# card-shuffling-dealing-machine.net
KiCad netlist of a schematic drawn in Altium Designer
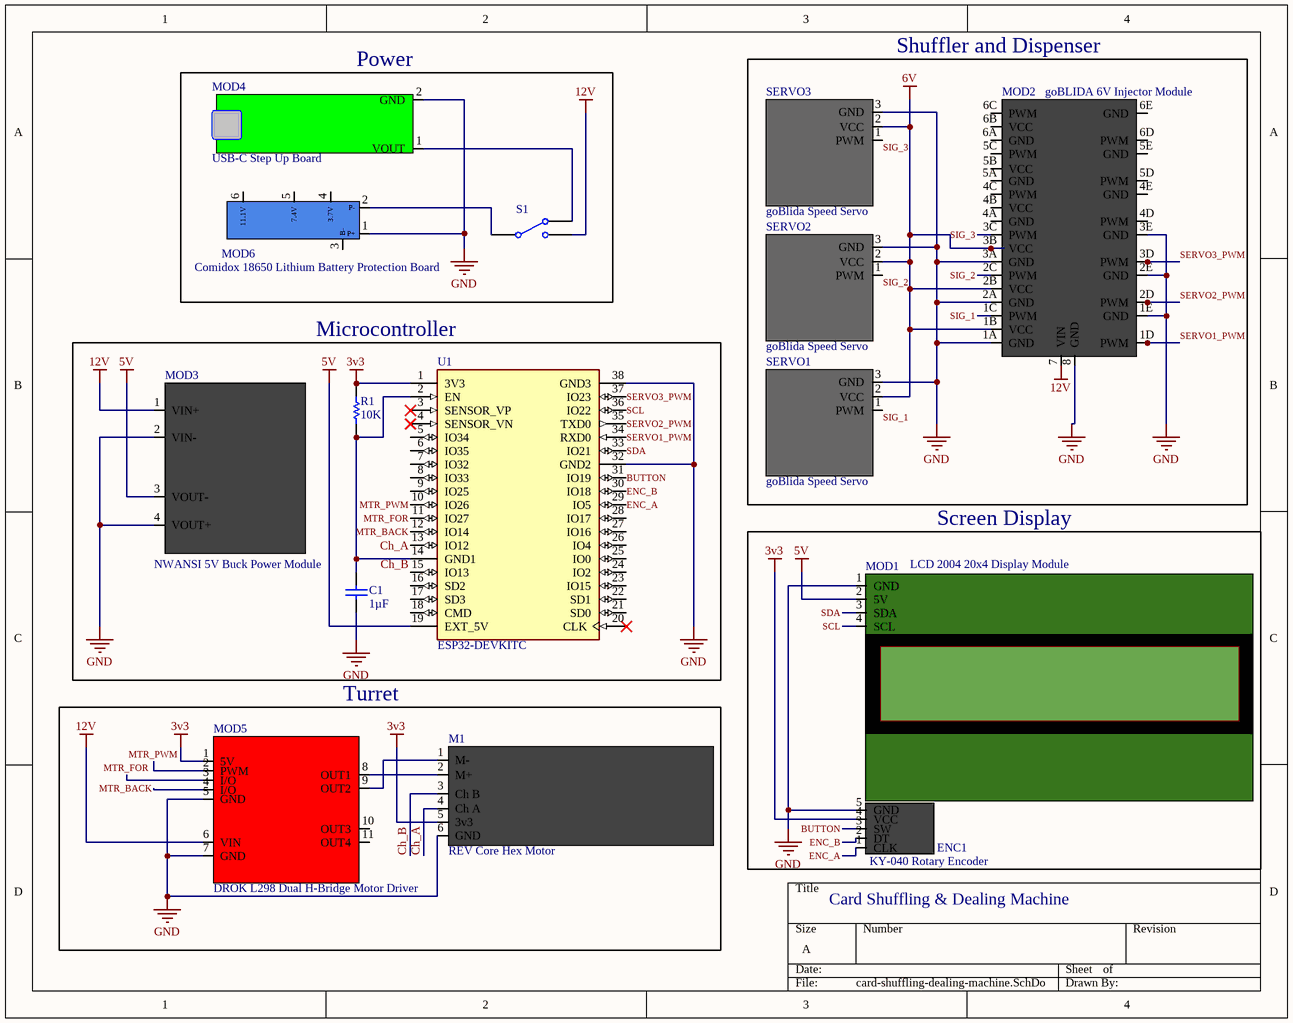
[diagram p0: card-shuffling-dealing-machine.SchDoc]

(export (version "E")
  (design (tool "Eeschema 10.0.6"))
  (components
    (comp (ref "C1")
      (value "1µF")
      (description "Capacitor")
      (libsource (lib "Simulation Generic Components") (part "Capacitor"))
    )
    (comp (ref "ENC1")
      (value "KY-040 Rotary Encoder")
      (description "5V Rotary Encoder Module 360 Degree Switch Encoder")
      (libsource (lib "CustomParts") (part "KY-040_Rotary_Encoder"))
    )
    (comp (ref "M1")
      (value "REV Core Hex Motor")
      (description "12 V DC Gear Motor with Integrated Encoder")
      (libsource (lib "CustomParts") (part "REV_Core_Hex_Motor"))
    )
    (comp (ref "MOD1")
      (value "LCD 2004 20x4 Display Module")
      (description "LCD 2004 I2C (TWI) 20x4 Display Module")
      (libsource (lib "CustomParts") (part "LCD_2004_20x4_Display_Module"))
    )
    (comp (ref "MOD2")
      (value "goBLIDA 6V Injector Module")
      (description "8-15V Input to 6V 24A Injector Module")
      (libsource (lib "CustomParts") (part "goBLIDA_6V_Injector_Module"))
    )
    (comp (ref "MOD3")
      (value "NWANSI 5V Buck Power Module")
      (description "DC 12/24V to 5V 3A/15W Power Converter Buck Power Module")
      (libsource (lib "CustomParts") (part "NWANSI_Buck_Power_Module"))
    )
    (comp (ref "MOD4")
      (value "USB-C Step Up Board")
      (description "Converts USB C 5V to 12.6V")
      (libsource (lib "CustomParts") (part "Type_C_Step_Up_Boost"))
    )
    (comp (ref "MOD5")
      (value "DROK L298 Dual H-Bridge Motor Driver")
      (description "7A Dual DC Motor Controller Board (6.5V-27V Input, Optocoupler Isolated)")
      (libsource (lib "CustomParts") (part "L298_Dual_H_Bridge_Motor_Driver"))
    )
    (comp (ref "MOD6")
      (value "Comidox 18650 Lithium Battery Protection Board")
      (description "3S 12V 10A 18650 Lithium Battery Protection Board")
      (libsource (lib "CustomParts") (part "Comidox_18650_Lithium_Battery_Protection_Board"))
    )
    (comp (ref "R1")
      (value "10K")
      (description "Resistor")
      (libsource (lib "Simulation Generic Components") (part "Resistor"))
    )
    (comp (ref "S1")
      (value "Single-Pole, Double-Throw Switch")
      (libsource (lib "Simulation Generic Components") (part "SPDT SW"))
    )
    (comp (ref "SERVO1")
      (value "goBlida Speed Servo")
      (description "Dual-Mode Servo (PWM/Continuous)")
      (libsource (lib "CustomParts") (part "goBIDA_Speed_Servo"))
    )
    (comp (ref "SERVO2")
      (value "goBlida Speed Servo")
      (description "Dual-Mode Servo (PWM/Continuous)")
      (libsource (lib "CustomParts") (part "goBIDA_Speed_Servo"))
    )
    (comp (ref "SERVO3")
      (value "goBlida Speed Servo")
      (description "Dual-Mode Servo (PWM/Continuous)")
      (libsource (lib "CustomParts") (part "goBIDA_Speed_Servo"))
    )
    (comp (ref "U1")
      (value "ESP32-DEVKITC")
      (footprint "MODULE_ESP32-DEVKITC")
      (fields (field (name "MF") "Espressif Systems"))
      (libsource (lib "Gaucho Racing") (part "ESP32-DEVKITC"))
    )
  )
  (nets
    (net (code "1") (name "/BUTTON") (class "Default")
      (node (ref "ENC1") (pin "3") (pinfunction "SW_3") (pintype "passive"))
      (node (ref "U1") (pin "31") (pinfunction "IO19_31") (pintype "bidirectional"))
    )
    (net (code "2") (name "/Ch_A") (class "Default")
      (node (ref "M1") (pin "4") (pinfunction "Ch_A_4") (pintype "passive"))
      (node (ref "U1") (pin "13") (pinfunction "IO12_13") (pintype "bidirectional"))
    )
    (net (code "3") (name "/Ch_B") (class "Default")
      (node (ref "M1") (pin "3") (pinfunction "Ch_B_3") (pintype "passive"))
      (node (ref "U1") (pin "15") (pinfunction "IO13_15") (pintype "bidirectional"))
    )
    (net (code "4") (name "/ENC_A") (class "Default")
      (node (ref "ENC1") (pin "1") (pinfunction "CLK_1") (pintype "passive"))
      (node (ref "U1") (pin "29") (pinfunction "IO5_29") (pintype "bidirectional"))
    )
    (net (code "5") (name "/ENC_B") (class "Default")
      (node (ref "ENC1") (pin "2") (pinfunction "DT_2") (pintype "passive"))
      (node (ref "U1") (pin "30") (pinfunction "IO18_30") (pintype "bidirectional"))
    )
    (net (code "6") (name "/MTR_BACK") (class "Default")
      (node (ref "MOD5") (pin "4") (pinfunction "I/O_4") (pintype "bidirectional"))
      (node (ref "U1") (pin "12") (pinfunction "IO14_12") (pintype "bidirectional"))
    )
    (net (code "7") (name "/MTR_FOR") (class "Default")
      (node (ref "MOD5") (pin "3") (pinfunction "I/O_3") (pintype "bidirectional"))
      (node (ref "U1") (pin "11") (pinfunction "IO27_11") (pintype "bidirectional"))
    )
    (net (code "8") (name "/MTR_PWM") (class "Default")
      (node (ref "MOD5") (pin "2") (pinfunction "PWM_2") (pintype "passive"))
      (node (ref "U1") (pin "10") (pinfunction "IO26_10") (pintype "bidirectional"))
    )
    (net (code "9") (name "/SCL") (class "Default")
      (node (ref "MOD1") (pin "4") (pinfunction "SCL_4") (pintype "passive"))
      (node (ref "U1") (pin "36") (pinfunction "IO22_36") (pintype "bidirectional"))
    )
    (net (code "10") (name "/SDA") (class "Default")
      (node (ref "MOD1") (pin "3") (pinfunction "SDA_3") (pintype "passive"))
      (node (ref "U1") (pin "33") (pinfunction "IO21_33") (pintype "bidirectional"))
    )
    (net (code "11") (name "/SERVO1_PWM") (class "Default")
      (node (ref "MOD2") (pin "1D") (pinfunction "PWM_1D") (pintype "passive"))
      (node (ref "U1") (pin "34") (pinfunction "RXD0_34") (pintype "input"))
    )
    (net (code "12") (name "/SERVO2_PWM") (class "Default")
      (node (ref "MOD2") (pin "2D") (pinfunction "PWM_2D") (pintype "passive"))
      (node (ref "U1") (pin "35") (pinfunction "TXD0_35") (pintype "output"))
    )
    (net (code "13") (name "/SERVO3_PWM") (class "Default")
      (node (ref "MOD2") (pin "3D") (pinfunction "PWM_3D") (pintype "passive"))
      (node (ref "U1") (pin "37") (pinfunction "IO23_37") (pintype "bidirectional"))
    )
    (net (code "14") (name "/SIG_1") (class "Default")
      (node (ref "MOD2") (pin "1C") (pinfunction "PWM_1C") (pintype "passive"))
      (node (ref "SERVO1") (pin "1") (pinfunction "PWM_1") (pintype "passive"))
    )
    (net (code "15") (name "/SIG_2") (class "Default")
      (node (ref "MOD2") (pin "2C") (pinfunction "PWM_2C") (pintype "passive"))
      (node (ref "SERVO2") (pin "1") (pinfunction "PWM_1") (pintype "passive"))
    )
    (net (code "16") (name "/SIG_3") (class "Default")
      (node (ref "MOD2") (pin "3C") (pinfunction "PWM_3C") (pintype "passive"))
      (node (ref "SERVO3") (pin "1") (pinfunction "PWM_1") (pintype "passive"))
    )
    (net (code "17") (name "3v3") (class "Default")
      (node (ref "ENC1") (pin "4") (pinfunction "VCC_4") (pintype "passive"))
      (node (ref "M1") (pin "5") (pinfunction "3v3_5") (pintype "passive"))
      (node (ref "MOD5") (pin "1") (pinfunction "5V_1") (pintype "passive"))
      (node (ref "R1") (pin "2") (pinfunction "2_2") (pintype "passive"))
      (node (ref "U1") (pin "1") (pinfunction "3V3_1") (pintype "power_in"))
    )
    (net (code "18") (name "5V") (class "Default")
      (node (ref "MOD1") (pin "2") (pinfunction "5V_2") (pintype "passive"))
      (node (ref "MOD3") (pin "3") (pinfunction "VOUT-_3") (pintype "power_in"))
      (node (ref "U1") (pin "19") (pinfunction "EXT_5V_19") (pintype "power_in"))
    )
    (net (code "19") (name "6V") (class "Default")
      (node (ref "MOD2") (pin "1B") (pinfunction "VCC_1B") (pintype "passive"))
      (node (ref "MOD2") (pin "2B") (pinfunction "VCC_2B") (pintype "passive"))
      (node (ref "MOD2") (pin "3B") (pinfunction "VCC_3B") (pintype "passive"))
      (node (ref "SERVO1") (pin "2") (pinfunction "VCC_2") (pintype "passive"))
      (node (ref "SERVO2") (pin "2") (pinfunction "VCC_2") (pintype "passive"))
      (node (ref "SERVO3") (pin "2") (pinfunction "VCC_2") (pintype "passive"))
    )
    (net (code "20") (name "12V") (class "Default")
      (node (ref "MOD2") (pin "7") (pinfunction "VIN_7") (pintype "passive"))
      (node (ref "MOD3") (pin "1") (pinfunction "VIN+_1") (pintype "input"))
      (node (ref "MOD5") (pin "6") (pinfunction "VIN_6") (pintype "passive"))
      (node (ref "S1") (pin "2") (pinfunction "2_2") (pintype "passive"))
    )
    (net (code "21") (name "GND") (class "Default")
      (node (ref "C1") (pin "1") (pinfunction "1_1") (pintype "passive"))
      (node (ref "ENC1") (pin "5") (pinfunction "GND_5") (pintype "passive"))
      (node (ref "M1") (pin "6") (pinfunction "GND_6") (pintype "passive"))
      (node (ref "MOD1") (pin "1") (pinfunction "GND_1") (pintype "passive"))
      (node (ref "MOD2") (pin "1A") (pinfunction "GND_1A") (pintype "passive"))
      (node (ref "MOD2") (pin "1E") (pinfunction "GND_1E") (pintype "passive"))
      (node (ref "MOD2") (pin "2A") (pinfunction "GND_2A") (pintype "passive"))
      (node (ref "MOD2") (pin "2E") (pinfunction "GND_2E") (pintype "passive"))
      (node (ref "MOD2") (pin "3A") (pinfunction "GND_3A") (pintype "passive"))
      (node (ref "MOD2") (pin "3E") (pinfunction "GND_3E") (pintype "passive"))
      (node (ref "MOD2") (pin "8") (pinfunction "GND_8") (pintype "passive"))
      (node (ref "MOD3") (pin "2") (pinfunction "VIN-_2") (pintype "input"))
      (node (ref "MOD3") (pin "4") (pinfunction "VOUT+_4") (pintype "power_in"))
      (node (ref "MOD4") (pin "2") (pinfunction "GND_2") (pintype "passive"))
      (node (ref "MOD5") (pin "5") (pinfunction "GND_5") (pintype "passive"))
      (node (ref "MOD5") (pin "7") (pinfunction "GND_7") (pintype "passive"))
      (node (ref "MOD6") (pin "1") (pinfunction "P+_1") (pintype "passive"))
      (node (ref "SERVO1") (pin "3") (pinfunction "GND_3") (pintype "passive"))
      (node (ref "SERVO2") (pin "3") (pinfunction "GND_3") (pintype "passive"))
      (node (ref "SERVO3") (pin "3") (pinfunction "GND_3") (pintype "passive"))
      (node (ref "U1") (pin "32") (pinfunction "GND2_32") (pintype "power_in"))
      (node (ref "U1") (pin "38") (pinfunction "GND3_38") (pintype "power_in"))
    )
    (net (code "22") (name "Net-(M1-M+)") (class "Default")
      (node (ref "M1") (pin "2") (pinfunction "M+_2") (pintype "passive"))
      (node (ref "MOD5") (pin "8") (pinfunction "OUT1_8") (pintype "output"))
    )
    (net (code "23") (name "Net-(M1-M-)") (class "Default")
      (node (ref "M1") (pin "1") (pinfunction "M-_1") (pintype "passive"))
      (node (ref "MOD5") (pin "9") (pinfunction "OUT2_9") (pintype "output"))
    )
    (net (code "24") (name "Net-(MOD4-VOUT)") (class "Default")
      (node (ref "MOD4") (pin "1") (pinfunction "VOUT_1") (pintype "passive"))
      (node (ref "S1") (pin "3") (pinfunction "3_3") (pintype "passive"))
    )
    (net (code "25") (name "Net-(MOD6-P-)") (class "Default")
      (node (ref "MOD6") (pin "2") (pinfunction "P-_2") (pintype "passive"))
      (node (ref "S1") (pin "1") (pinfunction "1_1") (pintype "passive"))
    )
    (net (code "26") (name "Net-(U1-EN)") (class "Default")
      (node (ref "C1") (pin "2") (pinfunction "2_2") (pintype "passive"))
      (node (ref "R1") (pin "1") (pinfunction "1_1") (pintype "passive"))
      (node (ref "U1") (pin "14") (pinfunction "GND1_14") (pintype "power_in"))
      (node (ref "U1") (pin "2") (pinfunction "EN_2") (pintype "input"))
    )
    (net (code "27") (name "unconnected-(MOD2-GND-Pad4A)") (class "Default")
      (node (ref "MOD2") (pin "4A") (pinfunction "GND_4A") (pintype "passive"))
    )
    (net (code "28") (name "unconnected-(MOD2-GND-Pad4E)") (class "Default")
      (node (ref "MOD2") (pin "4E") (pinfunction "GND_4E") (pintype "passive"))
    )
    (net (code "29") (name "unconnected-(MOD2-GND-Pad5A)") (class "Default")
      (node (ref "MOD2") (pin "5A") (pinfunction "GND_5A") (pintype "passive"))
    )
    (net (code "30") (name "unconnected-(MOD2-GND-Pad5E)") (class "Default")
      (node (ref "MOD2") (pin "5E") (pinfunction "GND_5E") (pintype "passive"))
    )
    (net (code "31") (name "unconnected-(MOD2-GND-Pad6A)") (class "Default")
      (node (ref "MOD2") (pin "6A") (pinfunction "GND_6A") (pintype "passive"))
    )
    (net (code "32") (name "unconnected-(MOD2-GND-Pad6E)") (class "Default")
      (node (ref "MOD2") (pin "6E") (pinfunction "GND_6E") (pintype "passive"))
    )
    (net (code "33") (name "unconnected-(MOD2-PWM-Pad4C)") (class "Default")
      (node (ref "MOD2") (pin "4C") (pinfunction "PWM_4C") (pintype "passive"))
    )
    (net (code "34") (name "unconnected-(MOD2-PWM-Pad4D)") (class "Default")
      (node (ref "MOD2") (pin "4D") (pinfunction "PWM_4D") (pintype "passive"))
    )
    (net (code "35") (name "unconnected-(MOD2-PWM-Pad5C)") (class "Default")
      (node (ref "MOD2") (pin "5C") (pinfunction "PWM_5C") (pintype "passive"))
    )
    (net (code "36") (name "unconnected-(MOD2-PWM-Pad5D)") (class "Default")
      (node (ref "MOD2") (pin "5D") (pinfunction "PWM_5D") (pintype "passive"))
    )
    (net (code "37") (name "unconnected-(MOD2-PWM-Pad6C)") (class "Default")
      (node (ref "MOD2") (pin "6C") (pinfunction "PWM_6C") (pintype "passive"))
    )
    (net (code "38") (name "unconnected-(MOD2-PWM-Pad6D)") (class "Default")
      (node (ref "MOD2") (pin "6D") (pinfunction "PWM_6D") (pintype "passive"))
    )
    (net (code "39") (name "unconnected-(MOD2-VCC-Pad4B)") (class "Default")
      (node (ref "MOD2") (pin "4B") (pinfunction "VCC_4B") (pintype "passive"))
    )
    (net (code "40") (name "unconnected-(MOD2-VCC-Pad5B)") (class "Default")
      (node (ref "MOD2") (pin "5B") (pinfunction "VCC_5B") (pintype "passive"))
    )
    (net (code "41") (name "unconnected-(MOD2-VCC-Pad6B)") (class "Default")
      (node (ref "MOD2") (pin "6B") (pinfunction "VCC_6B") (pintype "passive"))
    )
    (net (code "42") (name "unconnected-(MOD5-OUT3-Pad10)") (class "Default")
      (node (ref "MOD5") (pin "10") (pinfunction "OUT3_10") (pintype "output"))
    )
    (net (code "43") (name "unconnected-(MOD5-OUT4-Pad11)") (class "Default")
      (node (ref "MOD5") (pin "11") (pinfunction "OUT4_11") (pintype "output"))
    )
    (net (code "44") (name "unconnected-(MOD6-3.7V-Pad4)") (class "Default")
      (node (ref "MOD6") (pin "4") (pinfunction "3.7V_4") (pintype "passive"))
    )
    (net (code "45") (name "unconnected-(MOD6-7.4V-Pad5)") (class "Default")
      (node (ref "MOD6") (pin "5") (pinfunction "7.4V_5") (pintype "passive"))
    )
    (net (code "46") (name "unconnected-(MOD6-11.1V-Pad6)") (class "Default")
      (node (ref "MOD6") (pin "6") (pinfunction "11.1V_6") (pintype "passive"))
    )
    (net (code "47") (name "unconnected-(MOD6-B--Pad3)") (class "Default")
      (node (ref "MOD6") (pin "3") (pinfunction "B-_3") (pintype "passive"))
    )
    (net (code "48") (name "unconnected-(U1-CLK-Pad20)") (class "Default")
      (node (ref "U1") (pin "20") (pinfunction "CLK_20") (pintype "input+no_connect"))
    )
    (net (code "49") (name "unconnected-(U1-CMD-Pad18)") (class "Default")
      (node (ref "U1") (pin "18") (pinfunction "CMD_18") (pintype "bidirectional"))
    )
    (net (code "50") (name "unconnected-(U1-IO0-Pad25)") (class "Default")
      (node (ref "U1") (pin "25") (pinfunction "IO0_25") (pintype "bidirectional"))
    )
    (net (code "51") (name "unconnected-(U1-IO2-Pad24)") (class "Default")
      (node (ref "U1") (pin "24") (pinfunction "IO2_24") (pintype "bidirectional"))
    )
    (net (code "52") (name "unconnected-(U1-IO4-Pad26)") (class "Default")
      (node (ref "U1") (pin "26") (pinfunction "IO4_26") (pintype "bidirectional"))
    )
    (net (code "53") (name "unconnected-(U1-IO15-Pad23)") (class "Default")
      (node (ref "U1") (pin "23") (pinfunction "IO15_23") (pintype "bidirectional"))
    )
    (net (code "54") (name "unconnected-(U1-IO16-Pad27)") (class "Default")
      (node (ref "U1") (pin "27") (pinfunction "IO16_27") (pintype "bidirectional"))
    )
    (net (code "55") (name "unconnected-(U1-IO17-Pad28)") (class "Default")
      (node (ref "U1") (pin "28") (pinfunction "IO17_28") (pintype "bidirectional"))
    )
    (net (code "56") (name "unconnected-(U1-IO25-Pad9)") (class "Default")
      (node (ref "U1") (pin "9") (pinfunction "IO25_9") (pintype "bidirectional"))
    )
    (net (code "57") (name "unconnected-(U1-IO32-Pad7)") (class "Default")
      (node (ref "U1") (pin "7") (pinfunction "IO32_7") (pintype "bidirectional"))
    )
    (net (code "58") (name "unconnected-(U1-IO33-Pad8)") (class "Default")
      (node (ref "U1") (pin "8") (pinfunction "IO33_8") (pintype "bidirectional"))
    )
    (net (code "59") (name "unconnected-(U1-IO34-Pad5)") (class "Default")
      (node (ref "U1") (pin "5") (pinfunction "IO34_5") (pintype "bidirectional"))
    )
    (net (code "60") (name "unconnected-(U1-IO35-Pad6)") (class "Default")
      (node (ref "U1") (pin "6") (pinfunction "IO35_6") (pintype "bidirectional"))
    )
    (net (code "61") (name "unconnected-(U1-SD0-Pad21)") (class "Default")
      (node (ref "U1") (pin "21") (pinfunction "SD0_21") (pintype "bidirectional"))
    )
    (net (code "62") (name "unconnected-(U1-SD1-Pad22)") (class "Default")
      (node (ref "U1") (pin "22") (pinfunction "SD1_22") (pintype "bidirectional"))
    )
    (net (code "63") (name "unconnected-(U1-SD2-Pad16)") (class "Default")
      (node (ref "U1") (pin "16") (pinfunction "SD2_16") (pintype "bidirectional"))
    )
    (net (code "64") (name "unconnected-(U1-SD3-Pad17)") (class "Default")
      (node (ref "U1") (pin "17") (pinfunction "SD3_17") (pintype "bidirectional"))
    )
    (net (code "65") (name "unconnected-(U1-SENSOR_VN-Pad4)") (class "Default")
      (node (ref "U1") (pin "4") (pinfunction "SENSOR_VN_4") (pintype "input+no_connect"))
    )
    (net (code "66") (name "unconnected-(U1-SENSOR_VP-Pad3)") (class "Default")
      (node (ref "U1") (pin "3") (pinfunction "SENSOR_VP_3") (pintype "input+no_connect"))
    )
  )
)
